# power-sheet.net
KiCad netlist of a schematic drawn in Altium Designer
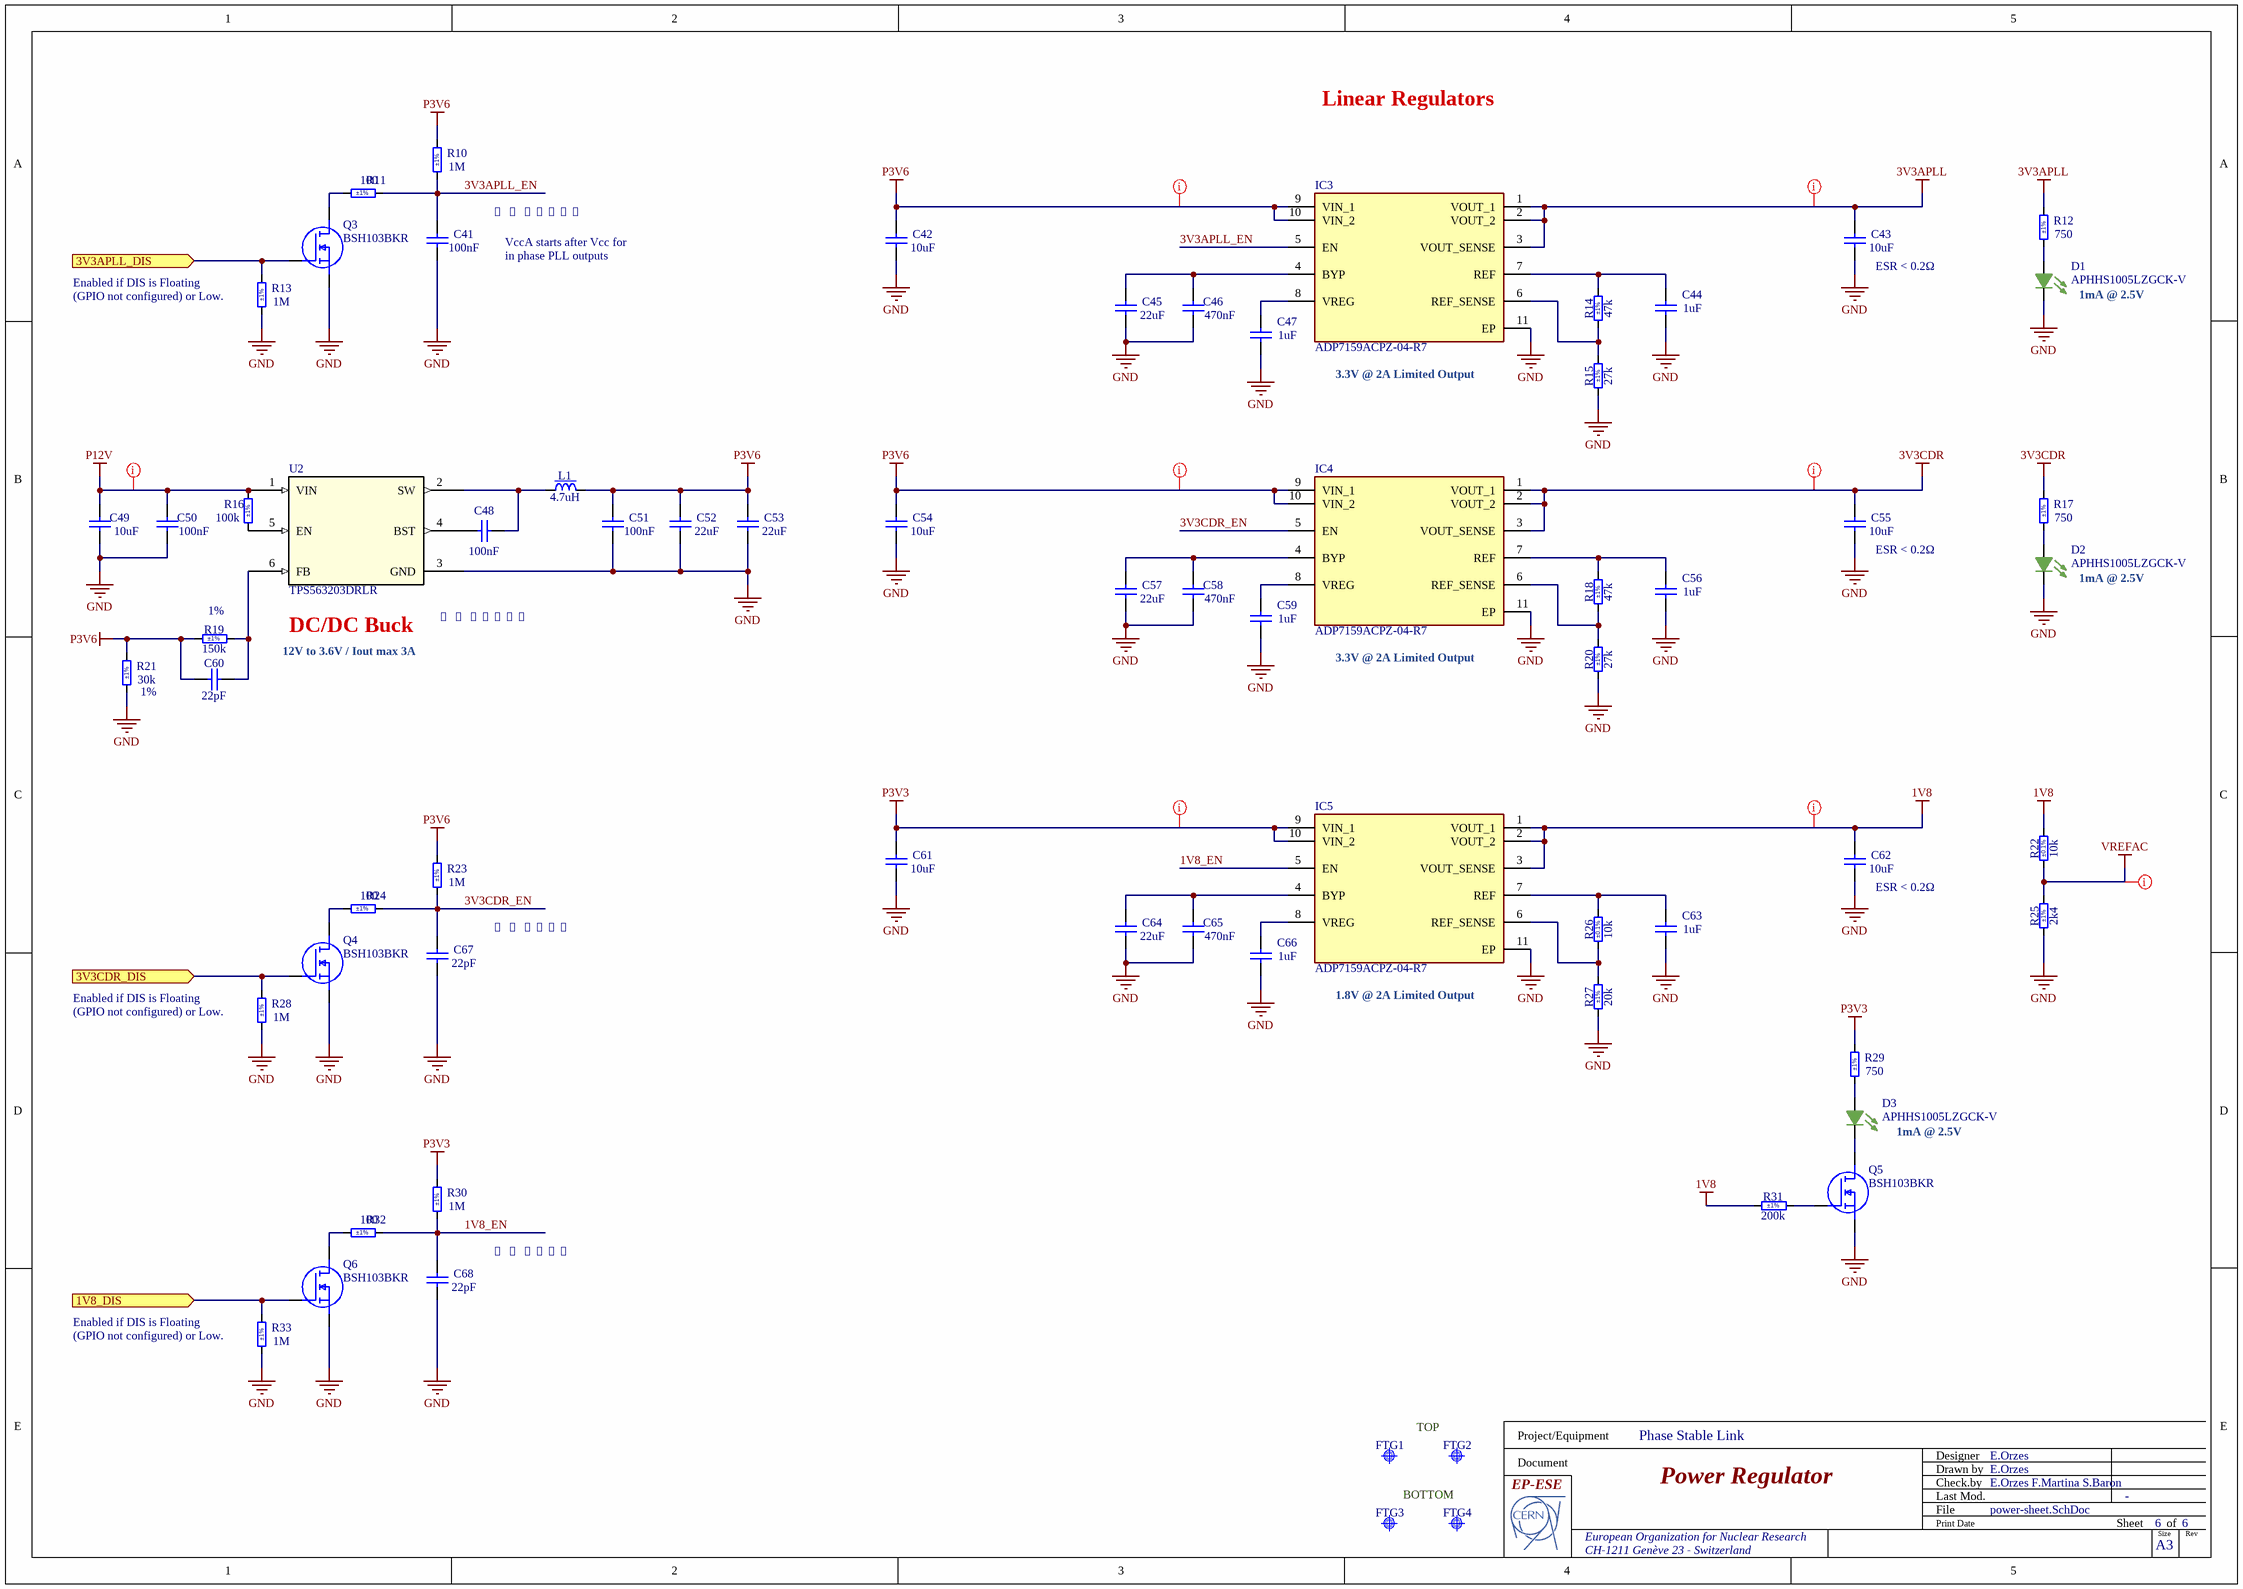
[diagram p0: power-sheet.SchDoc]

(export (version "E")
  (design (tool "Eeschema 10.0.6"))
  (components
    (comp (ref "C41")
      (value "100nF")
      (footprint "CAPC0603X33N")
      (description "GRM033R61C104KE14")
      (fields
        (field (name "PART NUMBER") "CC0201_100NF_6.3V_10%_X5R")
        (field (name "VOLTAGE") "6.3V")
        (field (name "AUTHOR") "CERN DEM JLC")
      )
      (libsource (lib "Capacitors") (part "Capacitor - non polarized"))
    )
    (comp (ref "C42")
      (value "10uF")
      (footprint "CAPC1608X87N")
      (description "GRM188D71A106KA73")
      (fields
        (field (name "PART NUMBER") "CC0603_10UF_6.3V_20%_X5R")
        (field (name "VOLTAGE") "6.3V")
        (field (name "AUTHOR") "CERN DEM JLC")
      )
      (libsource (lib "Capacitors") (part "Capacitor - non polarized"))
    )
    (comp (ref "C43")
      (value "10uF")
      (footprint "CAPC1608X87N")
      (description "GRM188D71A106KA73")
      (fields
        (field (name "PART NUMBER") "CC0603_10UF_6.3V_20%_X5R")
        (field (name "VOLTAGE") "6.3V")
        (field (name "AUTHOR") "CERN DEM JLC")
      )
      (libsource (lib "Capacitors") (part "Capacitor - non polarized"))
    )
    (comp (ref "C44")
      (value "1uF")
      (footprint "CAPC1005X55N")
      (description "GRM153B30J105ME15")
      (fields
        (field (name "PART NUMBER") "CC0402_1UF_16V_10%_X5R")
        (field (name "VOLTAGE") "16V")
        (field (name "AUTHOR") "CERN DEM JLC")
      )
      (libsource (lib "Capacitors") (part "Capacitor - non polarized"))
    )
    (comp (ref "C45")
      (value "22uF")
      (footprint "CAPC1005X70N")
      (description "GRM155R60J226ME11")
      (fields
        (field (name "PART NUMBER") "CC0402_10UF_6.3V_20%_X5R")
        (field (name "VOLTAGE") "6.3V")
        (field (name "AUTHOR") "CERN DEM JLC")
      )
      (libsource (lib "Capacitors") (part "Capacitor - non polarized"))
    )
    (comp (ref "C46")
      (value "470nF")
      (footprint "CAPC0510X04N")
      (description "LLL153C70G474ME17")
      (libsource (lib "auxiliary_library") (part "Capacitor - non polarized"))
    )
    (comp (ref "C47")
      (value "1uF")
      (footprint "CAPC1005X55N")
      (description "GRM153B30J105ME15")
      (fields
        (field (name "PART NUMBER") "CC0402_1UF_16V_10%_X5R")
        (field (name "VOLTAGE") "16V")
        (field (name "AUTHOR") "CERN DEM JLC")
      )
      (libsource (lib "Capacitors") (part "Capacitor - non polarized"))
    )
    (comp (ref "C48")
      (value "100nF")
      (footprint "CAPC0603X33N")
      (description "GRM033R61C104KE14")
      (fields
        (field (name "PART NUMBER") "CC0201_100NF_6.3V_10%_X5R")
        (field (name "VOLTAGE") "6.3V")
        (field (name "AUTHOR") "CERN DEM JLC")
      )
      (libsource (lib "Capacitors") (part "Capacitor - non polarized"))
    )
    (comp (ref "C49")
      (value "10uF")
      (footprint "CAPC2012X135N")
      (description "GRM21BR61C106KE15")
      (fields
        (field (name "PART NUMBER") "CC0805_10UF_16V_10%_X5R")
        (field (name "VOLTAGE") "16V")
        (field (name "AUTHOR") "CERN DEM JLC")
      )
      (libsource (lib "Capacitors") (part "Capacitor - non polarized"))
    )
    (comp (ref "C50")
      (value "100nF")
      (footprint "CAPC0603X33N")
      (description "GRM033R61C104KE14")
      (fields
        (field (name "PART NUMBER") "CC0201_100NF_6.3V_10%_X5R")
        (field (name "VOLTAGE") "6.3V")
        (field (name "AUTHOR") "CERN DEM JLC")
      )
      (libsource (lib "Capacitors") (part "Capacitor - non polarized"))
    )
    (comp (ref "C51")
      (value "100nF")
      (footprint "CAPC0603X33N")
      (description "GRM033R61C104KE14")
      (fields
        (field (name "PART NUMBER") "CC0201_100NF_6.3V_10%_X5R")
        (field (name "VOLTAGE") "6.3V")
        (field (name "AUTHOR") "CERN DEM JLC")
      )
      (libsource (lib "Capacitors") (part "Capacitor - non polarized"))
    )
    (comp (ref "C52")
      (value "22uF")
      (footprint "CAPC1005X70N")
      (description "GRM155R60J226ME11")
      (fields
        (field (name "PART NUMBER") "CC0402_10UF_6.3V_20%_X5R")
        (field (name "VOLTAGE") "6.3V")
        (field (name "AUTHOR") "CERN DEM JLC")
      )
      (libsource (lib "Capacitors") (part "Capacitor - non polarized"))
    )
    (comp (ref "C53")
      (value "22uF")
      (footprint "CAPC1005X70N")
      (description "GRM155R60J226ME11")
      (fields
        (field (name "PART NUMBER") "CC0402_10UF_6.3V_20%_X5R")
        (field (name "VOLTAGE") "6.3V")
        (field (name "AUTHOR") "CERN DEM JLC")
      )
      (libsource (lib "Capacitors") (part "Capacitor - non polarized"))
    )
    (comp (ref "C54")
      (value "10uF")
      (footprint "CAPC1608X87N")
      (description "GRM188D71A106KA73")
      (fields
        (field (name "PART NUMBER") "CC0603_10UF_6.3V_20%_X5R")
        (field (name "VOLTAGE") "6.3V")
        (field (name "AUTHOR") "CERN DEM JLC")
      )
      (libsource (lib "Capacitors") (part "Capacitor - non polarized"))
    )
    (comp (ref "C55")
      (value "10uF")
      (footprint "CAPC1608X87N")
      (description "GRM188D71A106KA73")
      (fields
        (field (name "PART NUMBER") "CC0603_10UF_6.3V_20%_X5R")
        (field (name "VOLTAGE") "6.3V")
        (field (name "AUTHOR") "CERN DEM JLC")
      )
      (libsource (lib "Capacitors") (part "Capacitor - non polarized"))
    )
    (comp (ref "C56")
      (value "1uF")
      (footprint "CAPC1005X55N")
      (description "GRM153B30J105ME15")
      (fields
        (field (name "PART NUMBER") "CC0402_1UF_16V_10%_X5R")
        (field (name "VOLTAGE") "16V")
        (field (name "AUTHOR") "CERN DEM JLC")
      )
      (libsource (lib "Capacitors") (part "Capacitor - non polarized"))
    )
    (comp (ref "C57")
      (value "22uF")
      (footprint "CAPC1005X70N")
      (description "GRM155R60J226ME11")
      (fields
        (field (name "PART NUMBER") "CC0402_10UF_6.3V_20%_X5R")
        (field (name "VOLTAGE") "6.3V")
        (field (name "AUTHOR") "CERN DEM JLC")
      )
      (libsource (lib "Capacitors") (part "Capacitor - non polarized"))
    )
    (comp (ref "C58")
      (value "470nF")
      (footprint "CAPC0510X04N")
      (description "LLL153C70G474ME17")
      (libsource (lib "auxiliary_library") (part "Capacitor - non polarized"))
    )
    (comp (ref "C59")
      (value "1uF")
      (footprint "CAPC1005X55N")
      (description "GRM153B30J105ME15")
      (fields
        (field (name "PART NUMBER") "CC0402_1UF_16V_10%_X5R")
        (field (name "VOLTAGE") "16V")
        (field (name "AUTHOR") "CERN DEM JLC")
      )
      (libsource (lib "Capacitors") (part "Capacitor - non polarized"))
    )
    (comp (ref "C60")
      (value "22pF")
      (footprint "CAPC0603X33N")
      (description "GJM0335C0J220GB01")
      (fields
        (field (name "PART NUMBER") "CC0201_4.7NF_10V_10%_X5R")
        (field (name "VOLTAGE") "10V")
        (field (name "AUTHOR") "CERN DEM JLC")
      )
      (libsource (lib "Capacitors") (part "Capacitor - non polarized"))
    )
    (comp (ref "C61")
      (value "10uF")
      (footprint "CAPC1608X87N")
      (description "GRM188D71A106KA73")
      (fields
        (field (name "PART NUMBER") "CC0603_10UF_6.3V_20%_X5R")
        (field (name "VOLTAGE") "6.3V")
        (field (name "AUTHOR") "CERN DEM JLC")
      )
      (libsource (lib "Capacitors") (part "Capacitor - non polarized"))
    )
    (comp (ref "C62")
      (value "10uF")
      (footprint "CAPC1608X87N")
      (description "GRM188D71A106KA73")
      (fields
        (field (name "PART NUMBER") "CC0603_10UF_6.3V_20%_X5R")
        (field (name "VOLTAGE") "6.3V")
        (field (name "AUTHOR") "CERN DEM JLC")
      )
      (libsource (lib "Capacitors") (part "Capacitor - non polarized"))
    )
    (comp (ref "C63")
      (value "1uF")
      (footprint "CAPC1005X55N")
      (description "GRM153B30J105ME15")
      (fields
        (field (name "PART NUMBER") "CC0402_1UF_16V_10%_X5R")
        (field (name "VOLTAGE") "16V")
        (field (name "AUTHOR") "CERN DEM JLC")
      )
      (libsource (lib "Capacitors") (part "Capacitor - non polarized"))
    )
    (comp (ref "C64")
      (value "22uF")
      (footprint "CAPC1005X70N")
      (description "GRM155R60J226ME11")
      (fields
        (field (name "PART NUMBER") "CC0402_10UF_6.3V_20%_X5R")
        (field (name "VOLTAGE") "6.3V")
        (field (name "AUTHOR") "CERN DEM JLC")
      )
      (libsource (lib "Capacitors") (part "Capacitor - non polarized"))
    )
    (comp (ref "C65")
      (value "470nF")
      (footprint "CAPC0510X04N")
      (description "LLL153C70G474ME17")
      (libsource (lib "auxiliary_library") (part "Capacitor - non polarized"))
    )
    (comp (ref "C66")
      (value "1uF")
      (footprint "CAPC1005X55N")
      (description "GRM153B30J105ME15")
      (fields
        (field (name "PART NUMBER") "CC0402_1UF_16V_10%_X5R")
        (field (name "VOLTAGE") "16V")
        (field (name "AUTHOR") "CERN DEM JLC")
      )
      (libsource (lib "Capacitors") (part "Capacitor - non polarized"))
    )
    (comp (ref "C67")
      (value "22pF")
      (footprint "CAPC0603X33N")
      (description "GJM0335C0J220GB01")
      (fields
        (field (name "PART NUMBER") "CC0201_4.7NF_10V_10%_X5R")
        (field (name "VOLTAGE") "10V")
        (field (name "AUTHOR") "CERN DEM JLC")
      )
      (libsource (lib "Capacitors") (part "Capacitor - non polarized"))
    )
    (comp (ref "C68")
      (value "22pF")
      (footprint "CAPC0603X33N")
      (description "GJM0335C0J220GB01")
      (fields
        (field (name "PART NUMBER") "CC0201_4.7NF_10V_10%_X5R")
        (field (name "VOLTAGE") "10V")
        (field (name "AUTHOR") "CERN DEM JLC")
      )
      (libsource (lib "Capacitors") (part "Capacitor - non polarized"))
    )
    (comp (ref "D1")
      (value "APHHS1005LZGCK-V")
      (footprint "LED_APHHS1005LZGCK-V")
      (description "Led Green 0402 2mA 2.65V 40mcd 102mW")
      (fields (field (name "MF") "Kingbright Corporation"))
      (libsource (lib "APHHS1005LZGCK-V") (part "APHHS1005LZGCK-V"))
    )
    (comp (ref "D2")
      (value "APHHS1005LZGCK-V")
      (footprint "LED_APHHS1005LZGCK-V")
      (description "Led Green 0402 2mA 2.65V 40mcd 102mW")
      (fields (field (name "MF") "Kingbright Corporation"))
      (libsource (lib "APHHS1005LZGCK-V") (part "APHHS1005LZGCK-V"))
    )
    (comp (ref "D3")
      (value "APHHS1005LZGCK-V")
      (footprint "LED_APHHS1005LZGCK-V")
      (description "Led Green 0402 2mA 2.65V 40mcd 102mW")
      (fields (field (name "MF") "Kingbright Corporation"))
      (libsource (lib "APHHS1005LZGCK-V") (part "APHHS1005LZGCK-V"))
    )
    (comp (ref "FTG1")
      (value "Use only in PCB")
      (footprint "FIDUCIAL_TOP_C100-200")
      (description "Fiducial Target")
      (fields (field (name "PART NUMBER") "FIDUCIAL_TARGET_C100-200") (field (name "AUTHOR") "CERN DEM JLC"))
      (libsource (lib "Eletro-mechanical") (part "Fiducial Target"))
    )
    (comp (ref "FTG2")
      (value "Use only in PCB")
      (footprint "FIDUCIAL_TOP_C100-200")
      (description "Fiducial Target")
      (fields (field (name "PART NUMBER") "FIDUCIAL_TARGET_C100-200") (field (name "AUTHOR") "CERN DEM JLC"))
      (libsource (lib "Eletro-mechanical") (part "Fiducial Target"))
    )
    (comp (ref "FTG3")
      (value "Use only in PCB")
      (footprint "FIDUCIAL_TOP_C100-200")
      (description "Fiducial Target")
      (fields (field (name "PART NUMBER") "FIDUCIAL_TARGET_C100-200") (field (name "AUTHOR") "CERN DEM JLC"))
      (libsource (lib "Eletro-mechanical") (part "Fiducial Target"))
    )
    (comp (ref "FTG4")
      (value "Use only in PCB")
      (footprint "FIDUCIAL_TOP_C100-200")
      (description "Fiducial Target")
      (fields (field (name "PART NUMBER") "FIDUCIAL_TARGET_C100-200") (field (name "AUTHOR") "CERN DEM JLC"))
      (libsource (lib "Eletro-mechanical") (part "Fiducial Target"))
    )
    (comp (ref "IC3")
      (value "ADP7159ACPZ-04-R7")
      (footprint "SamacSys:SON50P300X300X85-11N-D")
      (description "Integrated Circuit")
      (fields (field (name "MOUSER PART NUMBER") "584-ADP7159ACPZ04R7"))
      (libsource (lib "SamacSys") (part "ADP7159ACPZ-04-R7"))
    )
    (comp (ref "IC4")
      (value "ADP7159ACPZ-04-R7")
      (footprint "SamacSys:SON50P300X300X85-11N-D")
      (description "Integrated Circuit")
      (fields (field (name "MOUSER PART NUMBER") "584-ADP7159ACPZ04R7"))
      (libsource (lib "SamacSys") (part "ADP7159ACPZ-04-R7"))
    )
    (comp (ref "IC5")
      (value "ADP7159ACPZ-04-R7")
      (footprint "SamacSys:SON50P300X300X85-11N-D")
      (description "Integrated Circuit")
      (fields (field (name "MOUSER PART NUMBER") "584-ADP7159ACPZ04R7"))
      (libsource (lib "SamacSys") (part "ADP7159ACPZ-04-R7"))
    )
    (comp (ref "L1")
      (value "4.7uH")
      (footprint "IND_MURATA_LQH32C")
      (description "Inductor With Core")
      (fields
        (field (name "PART NUMBER") "IND_4.7UH_20%_MURATA_LQH32CN4R7M23L")
        (field (name "POWER") "450mA")
        (field (name "AUTHOR") "CERN DEM JLC")
      )
      (libsource (lib "Inductors & Transformers") (part "Inductor With Magnetic core"))
    )
    (comp (ref "Q3")
      (value "BSH103BKR")
      (footprint "SamacSys:SOT95P230X110-3N")
      (description "MOSFET (N-Channel)")
      (fields (field (name "MOUSER PART NUMBER") "771-BSH103BKR"))
      (libsource (lib "SamacSys") (part "BSH103BKR"))
    )
    (comp (ref "Q4")
      (value "BSH103BKR")
      (footprint "SamacSys:SOT95P230X110-3N")
      (description "MOSFET (N-Channel)")
      (fields (field (name "MOUSER PART NUMBER") "771-BSH103BKR"))
      (libsource (lib "SamacSys") (part "BSH103BKR"))
    )
    (comp (ref "Q5")
      (value "BSH103BKR")
      (footprint "SamacSys:SOT95P230X110-3N")
      (description "MOSFET (N-Channel)")
      (fields (field (name "MOUSER PART NUMBER") "771-BSH103BKR"))
      (libsource (lib "SamacSys") (part "BSH103BKR"))
    )
    (comp (ref "Q6")
      (value "BSH103BKR")
      (footprint "SamacSys:SOT95P230X110-3N")
      (description "MOSFET (N-Channel)")
      (fields (field (name "MOUSER PART NUMBER") "771-BSH103BKR"))
      (libsource (lib "SamacSys") (part "BSH103BKR"))
    )
    (comp (ref "R10")
      (value "1M")
      (footprint "RESC1005X40N")
      (description "Resistor - 1%")
      (fields
        (field (name "TOLERANCE") "±1%")
        (field (name "PART NUMBER") "R0402_1M_1%_0.0625W_100PPM")
        (field (name "POWER") "0.0625W")
        (field (name "AUTHOR") "CERN DEM JLC")
      )
      (libsource (lib "Resistors") (part "Resistor - 1%"))
    )
    (comp (ref "R11")
      (value "100")
      (footprint "RESC0603X28N")
      (description "Resistor - 1%")
      (fields
        (field (name "TOLERANCE") "±1%")
        (field (name "PART NUMBER") "R0201_100R_1%_0.05W_200PPM")
        (field (name "POWER") "0.05W")
        (field (name "AUTHOR") "CERN DEM JLC")
      )
      (libsource (lib "Resistors") (part "Resistor - 1%"))
    )
    (comp (ref "R12")
      (value "750")
      (footprint "RESC1005X40N")
      (description "Resistor - 1%")
      (fields
        (field (name "TOLERANCE") "±1%")
        (field (name "PART NUMBER") "R0402_750R_1%_0.0625W_100PPM")
        (field (name "POWER") "0.0625W")
        (field (name "AUTHOR") "CERN DEM JLC")
      )
      (libsource (lib "Resistors") (part "Resistor - 1%"))
    )
    (comp (ref "R13")
      (value "1M")
      (footprint "RESC1005X40N")
      (description "Resistor - 1%")
      (fields
        (field (name "TOLERANCE") "±1%")
        (field (name "PART NUMBER") "R0402_1M_1%_0.0625W_100PPM")
        (field (name "POWER") "0.0625W")
        (field (name "AUTHOR") "CERN DEM JLC")
      )
      (libsource (lib "Resistors") (part "Resistor - 1%"))
    )
    (comp (ref "R14")
      (value "47k")
      (footprint "RESC1005X40N")
      (description "Resistor - 1%")
      (fields
        (field (name "TOLERANCE") "±1%")
        (field (name "PART NUMBER") "R0402_47K_1%_0.0625W_100PPM")
        (field (name "POWER") "0.0625W")
        (field (name "AUTHOR") "CERN DEM JLC")
      )
      (libsource (lib "Resistors") (part "Resistor - 1%"))
    )
    (comp (ref "R15")
      (value "27k")
      (footprint "RESC1005X40N")
      (description "Resistor - 1%")
      (fields
        (field (name "TOLERANCE") "±1%")
        (field (name "PART NUMBER") "R0402_27K_1%_0.0625W_100PPM")
        (field (name "POWER") "0.0625W")
        (field (name "AUTHOR") "CERN DEM JLC")
      )
      (libsource (lib "Resistors") (part "Resistor - 1%"))
    )
    (comp (ref "R16")
      (value "100k")
      (footprint "RESC1005X40N")
      (description "Resistor - 1%")
      (fields
        (field (name "TOLERANCE") "±1%")
        (field (name "PART NUMBER") "R0402_100K_1%_0.0625W_100PPM")
        (field (name "POWER") "0.0625W")
        (field (name "AUTHOR") "CERN DEM JLC")
      )
      (libsource (lib "Resistors") (part "Resistor - 1%"))
    )
    (comp (ref "R17")
      (value "750")
      (footprint "RESC1005X40N")
      (description "Resistor - 1%")
      (fields
        (field (name "TOLERANCE") "±1%")
        (field (name "PART NUMBER") "R0402_750R_1%_0.0625W_100PPM")
        (field (name "POWER") "0.0625W")
        (field (name "AUTHOR") "CERN DEM JLC")
      )
      (libsource (lib "Resistors") (part "Resistor - 1%"))
    )
    (comp (ref "R18")
      (value "47k")
      (footprint "RESC1005X40N")
      (description "Resistor - 1%")
      (fields
        (field (name "TOLERANCE") "±1%")
        (field (name "PART NUMBER") "R0402_47K_1%_0.0625W_100PPM")
        (field (name "POWER") "0.0625W")
        (field (name "AUTHOR") "CERN DEM JLC")
      )
      (libsource (lib "Resistors") (part "Resistor - 1%"))
    )
    (comp (ref "R19")
      (value "150k")
      (footprint "RESC1608X55N")
      (description "Resistor - 1%")
      (fields
        (field (name "TOLERANCE") "±1%")
        (field (name "PART NUMBER") "R0603_150K_1%_0.1W_100PPM")
        (field (name "POWER") "0.1W")
        (field (name "AUTHOR") "CERN DEM JLC")
      )
      (libsource (lib "Resistors") (part "Resistor - 1%"))
    )
    (comp (ref "R20")
      (value "27k")
      (footprint "RESC1005X40N")
      (description "Resistor - 1%")
      (fields
        (field (name "TOLERANCE") "±1%")
        (field (name "PART NUMBER") "R0402_27K_1%_0.0625W_100PPM")
        (field (name "POWER") "0.0625W")
        (field (name "AUTHOR") "CERN DEM JLC")
      )
      (libsource (lib "Resistors") (part "Resistor - 1%"))
    )
    (comp (ref "R21")
      (value "30k")
      (footprint "RESC1608X55N")
      (description "Resistor - 1%")
      (fields
        (field (name "TOLERANCE") "±1%")
        (field (name "PART NUMBER") "R0603_30K_1%_0.1W_100PPM")
        (field (name "POWER") "0.1W")
        (field (name "AUTHOR") "CERN DEM JLC")
      )
      (libsource (lib "Resistors") (part "Resistor - 1%"))
    )
    (comp (ref "R22")
      (value "10k")
      (footprint "RESC3216X65N")
      (description "Resistor - 0.1%")
      (fields
        (field (name "TOLERANCE") "±0.1%")
        (field (name "PART NUMBER") "R1206_10K_0.1%_0.25W_25PPM")
        (field (name "POWER") "0.25W")
        (field (name "AUTHOR") "CERN DEM JLC")
      )
      (libsource (lib "Resistors") (part "Resistor - 0.1%"))
    )
    (comp (ref "R23")
      (value "1M")
      (footprint "RESC1005X40N")
      (description "Resistor - 1%")
      (fields
        (field (name "TOLERANCE") "±1%")
        (field (name "PART NUMBER") "R0402_1M_1%_0.0625W_100PPM")
        (field (name "POWER") "0.0625W")
        (field (name "AUTHOR") "CERN DEM JLC")
      )
      (libsource (lib "Resistors") (part "Resistor - 1%"))
    )
    (comp (ref "R24")
      (value "100")
      (footprint "RESC0603X28N")
      (description "Resistor - 1%")
      (fields
        (field (name "TOLERANCE") "±1%")
        (field (name "PART NUMBER") "R0201_100R_1%_0.05W_200PPM")
        (field (name "POWER") "0.05W")
        (field (name "AUTHOR") "CERN DEM JLC")
      )
      (libsource (lib "Resistors") (part "Resistor - 1%"))
    )
    (comp (ref "R25")
      (value "2k4")
      (footprint "RESC3216X65N")
      (description "Resistor - 1%")
      (fields
        (field (name "TOLERANCE") "±1%")
        (field (name "PART NUMBER") "R1206_2K4_1%_0.25W_100PPM")
        (field (name "POWER") "0.25W")
        (field (name "AUTHOR") "CERN DEM JLC")
      )
      (libsource (lib "Resistors") (part "Resistor - 1%"))
    )
    (comp (ref "R26")
      (value "10k")
      (footprint "RESC1005X35N")
      (description "Resistor - 0.1%")
      (fields
        (field (name "TOLERANCE") "±0.1%")
        (field (name "PART NUMBER") "R0402_10K_0.1%_0.063W_25PPM")
        (field (name "POWER") "0.063W")
        (field (name "AUTHOR") "CERN DEM JMW")
      )
      (libsource (lib "Resistors") (part "Resistor - 0.1%"))
    )
    (comp (ref "R27")
      (value "20k")
      (footprint "RESC1005X40N")
      (description "Resistor - 1%")
      (fields
        (field (name "TOLERANCE") "±1%")
        (field (name "PART NUMBER") "R0402_20K_1%_0.0625W_100PPM")
        (field (name "POWER") "0.0625W")
        (field (name "AUTHOR") "CERN DEM JLC")
      )
      (libsource (lib "Resistors") (part "Resistor - 1%"))
    )
    (comp (ref "R28")
      (value "1M")
      (footprint "RESC1005X40N")
      (description "Resistor - 1%")
      (fields
        (field (name "TOLERANCE") "±1%")
        (field (name "PART NUMBER") "R0402_1M_1%_0.0625W_100PPM")
        (field (name "POWER") "0.0625W")
        (field (name "AUTHOR") "CERN DEM JLC")
      )
      (libsource (lib "Resistors") (part "Resistor - 1%"))
    )
    (comp (ref "R29")
      (value "750")
      (footprint "RESC1005X40N")
      (description "Resistor - 1%")
      (fields
        (field (name "TOLERANCE") "±1%")
        (field (name "PART NUMBER") "R0402_750R_1%_0.0625W_100PPM")
        (field (name "POWER") "0.0625W")
        (field (name "AUTHOR") "CERN DEM JLC")
      )
      (libsource (lib "Resistors") (part "Resistor - 1%"))
    )
    (comp (ref "R30")
      (value "1M")
      (footprint "RESC1005X40N")
      (description "Resistor - 1%")
      (fields
        (field (name "TOLERANCE") "±1%")
        (field (name "PART NUMBER") "R0402_1M_1%_0.0625W_100PPM")
        (field (name "POWER") "0.0625W")
        (field (name "AUTHOR") "CERN DEM JLC")
      )
      (libsource (lib "Resistors") (part "Resistor - 1%"))
    )
    (comp (ref "R31")
      (value "200k")
      (footprint "RESC1005X40N")
      (description "Resistor - 1%")
      (fields
        (field (name "TOLERANCE") "±1%")
        (field (name "PART NUMBER") "R0402_200K_1%_0.0625W_100PPM")
        (field (name "POWER") "0.0625W")
        (field (name "AUTHOR") "CERN DEM JLC")
      )
      (libsource (lib "Resistors") (part "Resistor - 1%"))
    )
    (comp (ref "R32")
      (value "100")
      (footprint "RESC0603X28N")
      (description "Resistor - 1%")
      (fields
        (field (name "TOLERANCE") "±1%")
        (field (name "PART NUMBER") "R0201_100R_1%_0.05W_200PPM")
        (field (name "POWER") "0.05W")
        (field (name "AUTHOR") "CERN DEM JLC")
      )
      (libsource (lib "Resistors") (part "Resistor - 1%"))
    )
    (comp (ref "R33")
      (value "1M")
      (footprint "RESC1005X40N")
      (description "Resistor - 1%")
      (fields
        (field (name "TOLERANCE") "±1%")
        (field (name "PART NUMBER") "R0402_1M_1%_0.0625W_100PPM")
        (field (name "POWER") "0.0625W")
        (field (name "AUTHOR") "CERN DEM JLC")
      )
      (libsource (lib "Resistors") (part "Resistor - 1%"))
    )
    (comp (ref "U2")
      (value "TPS563203DRLR")
      (footprint "TPS563203DRLR:SOT_07SDRLR_TEX")
      (description "No Description Available")
      (libsource (lib "TPS563203DRLR") (part "TPS563203DRLR"))
    )
  )
  (nets
    (net (code "1") (name "/1V8_DIS") (class "Default")
      (node (ref "Q6") (pin "1") (pinfunction "G_1") (pintype "passive"))
      (node (ref "R33") (pin "2") (pinfunction "2_2") (pintype "passive"))
    )
    (net (code "2") (name "/1V8_EN") (class "Default")
      (node (ref "C68") (pin "2") (pinfunction "2_2") (pintype "passive"))
      (node (ref "IC5") (pin "5") (pinfunction "EN_5") (pintype "passive"))
      (node (ref "R30") (pin "1") (pinfunction "1_1") (pintype "passive"))
      (node (ref "R32") (pin "2") (pinfunction "2_2") (pintype "passive"))
    )
    (net (code "3") (name "/3V3APLL_DIS") (class "Default")
      (node (ref "Q3") (pin "1") (pinfunction "G_1") (pintype "passive"))
      (node (ref "R13") (pin "2") (pinfunction "2_2") (pintype "passive"))
    )
    (net (code "4") (name "/3V3APLL_EN") (class "Default")
      (node (ref "C41") (pin "2") (pinfunction "2_2") (pintype "passive"))
      (node (ref "IC3") (pin "5") (pinfunction "EN_5") (pintype "passive"))
      (node (ref "R10") (pin "1") (pinfunction "1_1") (pintype "passive"))
      (node (ref "R11") (pin "2") (pinfunction "2_2") (pintype "passive"))
    )
    (net (code "5") (name "/3V3CDR_DIS") (class "Default")
      (node (ref "Q4") (pin "1") (pinfunction "G_1") (pintype "passive"))
      (node (ref "R28") (pin "2") (pinfunction "2_2") (pintype "passive"))
    )
    (net (code "6") (name "/3V3CDR_EN") (class "Default")
      (node (ref "C67") (pin "2") (pinfunction "2_2") (pintype "passive"))
      (node (ref "IC4") (pin "5") (pinfunction "EN_5") (pintype "passive"))
      (node (ref "R23") (pin "1") (pinfunction "1_1") (pintype "passive"))
      (node (ref "R24") (pin "2") (pinfunction "2_2") (pintype "passive"))
    )
    (net (code "7") (name "1V8") (class "Default")
      (node (ref "C62") (pin "2") (pinfunction "2_2") (pintype "passive"))
      (node (ref "IC5") (pin "1") (pinfunction "VOUT_1_1") (pintype "passive"))
      (node (ref "IC5") (pin "2") (pinfunction "VOUT_2_2") (pintype "passive"))
      (node (ref "IC5") (pin "3") (pinfunction "VOUT_SENSE_3") (pintype "passive"))
      (node (ref "R22") (pin "2") (pinfunction "2_2") (pintype "passive"))
      (node (ref "R31") (pin "1") (pinfunction "1_1") (pintype "passive"))
    )
    (net (code "8") (name "3V3APLL") (class "Default")
      (node (ref "C43") (pin "2") (pinfunction "2_2") (pintype "passive"))
      (node (ref "IC3") (pin "1") (pinfunction "VOUT_1_1") (pintype "passive"))
      (node (ref "IC3") (pin "2") (pinfunction "VOUT_2_2") (pintype "passive"))
      (node (ref "IC3") (pin "3") (pinfunction "VOUT_SENSE_3") (pintype "passive"))
      (node (ref "R12") (pin "2") (pinfunction "2_2") (pintype "passive"))
    )
    (net (code "9") (name "3V3CDR") (class "Default")
      (node (ref "C55") (pin "2") (pinfunction "2_2") (pintype "passive"))
      (node (ref "IC4") (pin "1") (pinfunction "VOUT_1_1") (pintype "passive"))
      (node (ref "IC4") (pin "2") (pinfunction "VOUT_2_2") (pintype "passive"))
      (node (ref "IC4") (pin "3") (pinfunction "VOUT_SENSE_3") (pintype "passive"))
      (node (ref "R17") (pin "2") (pinfunction "2_2") (pintype "passive"))
    )
    (net (code "10") (name "GND") (class "Default")
      (node (ref "C41") (pin "1") (pinfunction "1_1") (pintype "passive"))
      (node (ref "C42") (pin "1") (pinfunction "1_1") (pintype "passive"))
      (node (ref "C43") (pin "1") (pinfunction "1_1") (pintype "passive"))
      (node (ref "C44") (pin "1") (pinfunction "1_1") (pintype "passive"))
      (node (ref "C45") (pin "1") (pinfunction "1_1") (pintype "passive"))
      (node (ref "C46") (pin "1") (pinfunction "1_1") (pintype "passive"))
      (node (ref "C47") (pin "1") (pinfunction "1_1") (pintype "passive"))
      (node (ref "C49") (pin "1") (pinfunction "1_1") (pintype "passive"))
      (node (ref "C50") (pin "1") (pinfunction "1_1") (pintype "passive"))
      (node (ref "C51") (pin "1") (pinfunction "1_1") (pintype "passive"))
      (node (ref "C52") (pin "1") (pinfunction "1_1") (pintype "passive"))
      (node (ref "C53") (pin "1") (pinfunction "1_1") (pintype "passive"))
      (node (ref "C54") (pin "1") (pinfunction "1_1") (pintype "passive"))
      (node (ref "C55") (pin "1") (pinfunction "1_1") (pintype "passive"))
      (node (ref "C56") (pin "1") (pinfunction "1_1") (pintype "passive"))
      (node (ref "C57") (pin "1") (pinfunction "1_1") (pintype "passive"))
      (node (ref "C58") (pin "1") (pinfunction "1_1") (pintype "passive"))
      (node (ref "C59") (pin "1") (pinfunction "1_1") (pintype "passive"))
      (node (ref "C61") (pin "1") (pinfunction "1_1") (pintype "passive"))
      (node (ref "C62") (pin "1") (pinfunction "1_1") (pintype "passive"))
      (node (ref "C63") (pin "1") (pinfunction "1_1") (pintype "passive"))
      (node (ref "C64") (pin "1") (pinfunction "1_1") (pintype "passive"))
      (node (ref "C65") (pin "1") (pinfunction "1_1") (pintype "passive"))
      (node (ref "C66") (pin "1") (pinfunction "1_1") (pintype "passive"))
      (node (ref "C67") (pin "1") (pinfunction "1_1") (pintype "passive"))
      (node (ref "C68") (pin "1") (pinfunction "1_1") (pintype "passive"))
      (node (ref "D1") (pin "1") (pinfunction "C_1") (pintype "passive"))
      (node (ref "D2") (pin "1") (pinfunction "C_1") (pintype "passive"))
      (node (ref "IC3") (pin "11") (pinfunction "EP_11") (pintype "passive"))
      (node (ref "IC4") (pin "11") (pinfunction "EP_11") (pintype "passive"))
      (node (ref "IC5") (pin "11") (pinfunction "EP_11") (pintype "passive"))
      (node (ref "Q3") (pin "2") (pinfunction "S_2") (pintype "passive"))
      (node (ref "Q4") (pin "2") (pinfunction "S_2") (pintype "passive"))
      (node (ref "Q5") (pin "2") (pinfunction "S_2") (pintype "passive"))
      (node (ref "Q6") (pin "2") (pinfunction "S_2") (pintype "passive"))
      (node (ref "R13") (pin "1") (pinfunction "1_1") (pintype "passive"))
      (node (ref "R15") (pin "1") (pinfunction "1_1") (pintype "passive"))
      (node (ref "R20") (pin "1") (pinfunction "1_1") (pintype "passive"))
      (node (ref "R21") (pin "1") (pinfunction "1_1") (pintype "passive"))
      (node (ref "R25") (pin "1") (pinfunction "1_1") (pintype "passive"))
      (node (ref "R27") (pin "1") (pinfunction "1_1") (pintype "passive"))
      (node (ref "R28") (pin "1") (pinfunction "1_1") (pintype "passive"))
      (node (ref "R33") (pin "1") (pinfunction "1_1") (pintype "passive"))
      (node (ref "U2") (pin "3") (pinfunction "GND_3") (pintype "power_in"))
    )
    (net (code "11") (name "Net-(D1-A)") (class "Default")
      (node (ref "D1") (pin "2") (pinfunction "A_2") (pintype "passive"))
      (node (ref "R12") (pin "1") (pinfunction "1_1") (pintype "passive"))
    )
    (net (code "12") (name "Net-(D2-A)") (class "Default")
      (node (ref "D2") (pin "2") (pinfunction "A_2") (pintype "passive"))
      (node (ref "R17") (pin "1") (pinfunction "1_1") (pintype "passive"))
    )
    (net (code "13") (name "Net-(D3-A)") (class "Default")
      (node (ref "D3") (pin "2") (pinfunction "A_2") (pintype "passive"))
      (node (ref "R29") (pin "1") (pinfunction "1_1") (pintype "passive"))
    )
    (net (code "14") (name "Net-(D3-C)") (class "Default")
      (node (ref "D3") (pin "1") (pinfunction "C_1") (pintype "passive"))
      (node (ref "Q5") (pin "3") (pinfunction "D_3") (pintype "passive"))
    )
    (net (code "15") (name "Net-(IC3-BYP)") (class "Default")
      (node (ref "C45") (pin "2") (pinfunction "2_2") (pintype "passive"))
      (node (ref "C46") (pin "2") (pinfunction "2_2") (pintype "passive"))
      (node (ref "IC3") (pin "4") (pinfunction "BYP_4") (pintype "passive"))
    )
    (net (code "16") (name "Net-(IC3-REF)") (class "Default")
      (node (ref "C44") (pin "2") (pinfunction "2_2") (pintype "passive"))
      (node (ref "IC3") (pin "7") (pinfunction "REF_7") (pintype "passive"))
      (node (ref "R14") (pin "2") (pinfunction "2_2") (pintype "passive"))
    )
    (net (code "17") (name "Net-(IC3-REF_SENSE)") (class "Default")
      (node (ref "IC3") (pin "6") (pinfunction "REF_SENSE_6") (pintype "passive"))
      (node (ref "R14") (pin "1") (pinfunction "1_1") (pintype "passive"))
      (node (ref "R15") (pin "2") (pinfunction "2_2") (pintype "passive"))
    )
    (net (code "18") (name "Net-(IC3-VREG)") (class "Default")
      (node (ref "C47") (pin "2") (pinfunction "2_2") (pintype "passive"))
      (node (ref "IC3") (pin "8") (pinfunction "VREG_8") (pintype "passive"))
    )
    (net (code "19") (name "Net-(IC4-BYP)") (class "Default")
      (node (ref "C57") (pin "2") (pinfunction "2_2") (pintype "passive"))
      (node (ref "C58") (pin "2") (pinfunction "2_2") (pintype "passive"))
      (node (ref "IC4") (pin "4") (pinfunction "BYP_4") (pintype "passive"))
    )
    (net (code "20") (name "Net-(IC4-REF)") (class "Default")
      (node (ref "C56") (pin "2") (pinfunction "2_2") (pintype "passive"))
      (node (ref "IC4") (pin "7") (pinfunction "REF_7") (pintype "passive"))
      (node (ref "R18") (pin "2") (pinfunction "2_2") (pintype "passive"))
    )
    (net (code "21") (name "Net-(IC4-REF_SENSE)") (class "Default")
      (node (ref "IC4") (pin "6") (pinfunction "REF_SENSE_6") (pintype "passive"))
      (node (ref "R18") (pin "1") (pinfunction "1_1") (pintype "passive"))
      (node (ref "R20") (pin "2") (pinfunction "2_2") (pintype "passive"))
    )
    (net (code "22") (name "Net-(IC4-VREG)") (class "Default")
      (node (ref "C59") (pin "2") (pinfunction "2_2") (pintype "passive"))
      (node (ref "IC4") (pin "8") (pinfunction "VREG_8") (pintype "passive"))
    )
    (net (code "23") (name "Net-(IC5-BYP)") (class "Default")
      (node (ref "C64") (pin "2") (pinfunction "2_2") (pintype "passive"))
      (node (ref "C65") (pin "2") (pinfunction "2_2") (pintype "passive"))
      (node (ref "IC5") (pin "4") (pinfunction "BYP_4") (pintype "passive"))
    )
    (net (code "24") (name "Net-(IC5-REF)") (class "Default")
      (node (ref "C63") (pin "2") (pinfunction "2_2") (pintype "passive"))
      (node (ref "IC5") (pin "7") (pinfunction "REF_7") (pintype "passive"))
      (node (ref "R26") (pin "2") (pinfunction "2_2") (pintype "passive"))
    )
    (net (code "25") (name "Net-(IC5-REF_SENSE)") (class "Default")
      (node (ref "IC5") (pin "6") (pinfunction "REF_SENSE_6") (pintype "passive"))
      (node (ref "R26") (pin "1") (pinfunction "1_1") (pintype "passive"))
      (node (ref "R27") (pin "2") (pinfunction "2_2") (pintype "passive"))
    )
    (net (code "26") (name "Net-(IC5-VREG)") (class "Default")
      (node (ref "C66") (pin "2") (pinfunction "2_2") (pintype "passive"))
      (node (ref "IC5") (pin "8") (pinfunction "VREG_8") (pintype "passive"))
    )
    (net (code "27") (name "Net-(Q3-D)") (class "Default")
      (node (ref "Q3") (pin "3") (pinfunction "D_3") (pintype "passive"))
      (node (ref "R11") (pin "1") (pinfunction "1_1") (pintype "passive"))
    )
    (net (code "28") (name "Net-(Q4-D)") (class "Default")
      (node (ref "Q4") (pin "3") (pinfunction "D_3") (pintype "passive"))
      (node (ref "R24") (pin "1") (pinfunction "1_1") (pintype "passive"))
    )
    (net (code "29") (name "Net-(Q5-G)") (class "Default")
      (node (ref "Q5") (pin "1") (pinfunction "G_1") (pintype "passive"))
      (node (ref "R31") (pin "2") (pinfunction "2_2") (pintype "passive"))
    )
    (net (code "30") (name "Net-(Q6-D)") (class "Default")
      (node (ref "Q6") (pin "3") (pinfunction "D_3") (pintype "passive"))
      (node (ref "R32") (pin "1") (pinfunction "1_1") (pintype "passive"))
    )
    (net (code "31") (name "Net-(U2-BST)") (class "Default")
      (node (ref "C48") (pin "2") (pinfunction "2_2") (pintype "passive"))
      (node (ref "U2") (pin "4") (pinfunction "BST_4") (pintype "output"))
    )
    (net (code "32") (name "Net-(U2-EN)") (class "Default")
      (node (ref "R16") (pin "1") (pinfunction "1_1") (pintype "passive"))
      (node (ref "U2") (pin "5") (pinfunction "EN_5") (pintype "input"))
    )
    (net (code "33") (name "Net-(U2-FB)") (class "Default")
      (node (ref "C60") (pin "2") (pinfunction "2_2") (pintype "passive"))
      (node (ref "R19") (pin "2") (pinfunction "2_2") (pintype "passive"))
      (node (ref "U2") (pin "6") (pinfunction "FB_6") (pintype "input"))
    )
    (net (code "34") (name "Net-(U2-SW)") (class "Default")
      (node (ref "C48") (pin "1") (pinfunction "1_1") (pintype "passive"))
      (node (ref "L1") (pin "1") (pinfunction "1_1") (pintype "passive"))
      (node (ref "U2") (pin "2") (pinfunction "SW_2") (pintype "output"))
    )
    (net (code "35") (name "P3V3") (class "Default")
      (node (ref "C61") (pin "2") (pinfunction "2_2") (pintype "passive"))
      (node (ref "IC5") (pin "10") (pinfunction "VIN_2_10") (pintype "passive"))
      (node (ref "IC5") (pin "9") (pinfunction "VIN_1_9") (pintype "passive"))
      (node (ref "R29") (pin "2") (pinfunction "2_2") (pintype "passive"))
      (node (ref "R30") (pin "2") (pinfunction "2_2") (pintype "passive"))
    )
    (net (code "36") (name "P3V6") (class "Default")
      (node (ref "C42") (pin "2") (pinfunction "2_2") (pintype "passive"))
      (node (ref "C51") (pin "2") (pinfunction "2_2") (pintype "passive"))
      (node (ref "C52") (pin "2") (pinfunction "2_2") (pintype "passive"))
      (node (ref "C53") (pin "2") (pinfunction "2_2") (pintype "passive"))
      (node (ref "C54") (pin "2") (pinfunction "2_2") (pintype "passive"))
      (node (ref "C60") (pin "1") (pinfunction "1_1") (pintype "passive"))
      (node (ref "IC3") (pin "10") (pinfunction "VIN_2_10") (pintype "passive"))
      (node (ref "IC3") (pin "9") (pinfunction "VIN_1_9") (pintype "passive"))
      (node (ref "IC4") (pin "10") (pinfunction "VIN_2_10") (pintype "passive"))
      (node (ref "IC4") (pin "9") (pinfunction "VIN_1_9") (pintype "passive"))
      (node (ref "L1") (pin "2") (pinfunction "2_2") (pintype "passive"))
      (node (ref "R10") (pin "2") (pinfunction "2_2") (pintype "passive"))
      (node (ref "R19") (pin "1") (pinfunction "1_1") (pintype "passive"))
      (node (ref "R21") (pin "2") (pinfunction "2_2") (pintype "passive"))
      (node (ref "R23") (pin "2") (pinfunction "2_2") (pintype "passive"))
    )
    (net (code "37") (name "P12V") (class "Default")
      (node (ref "C49") (pin "2") (pinfunction "2_2") (pintype "passive"))
      (node (ref "C50") (pin "2") (pinfunction "2_2") (pintype "passive"))
      (node (ref "R16") (pin "2") (pinfunction "2_2") (pintype "passive"))
      (node (ref "U2") (pin "1") (pinfunction "VIN_1") (pintype "input"))
    )
    (net (code "38") (name "VREFAC") (class "Default")
      (node (ref "R22") (pin "1") (pinfunction "1_1") (pintype "passive"))
      (node (ref "R25") (pin "2") (pinfunction "2_2") (pintype "passive"))
    )
  )
)
